# 16_BoardPowerSupply.net
KiCad netlist of a schematic drawn in Altium Designer
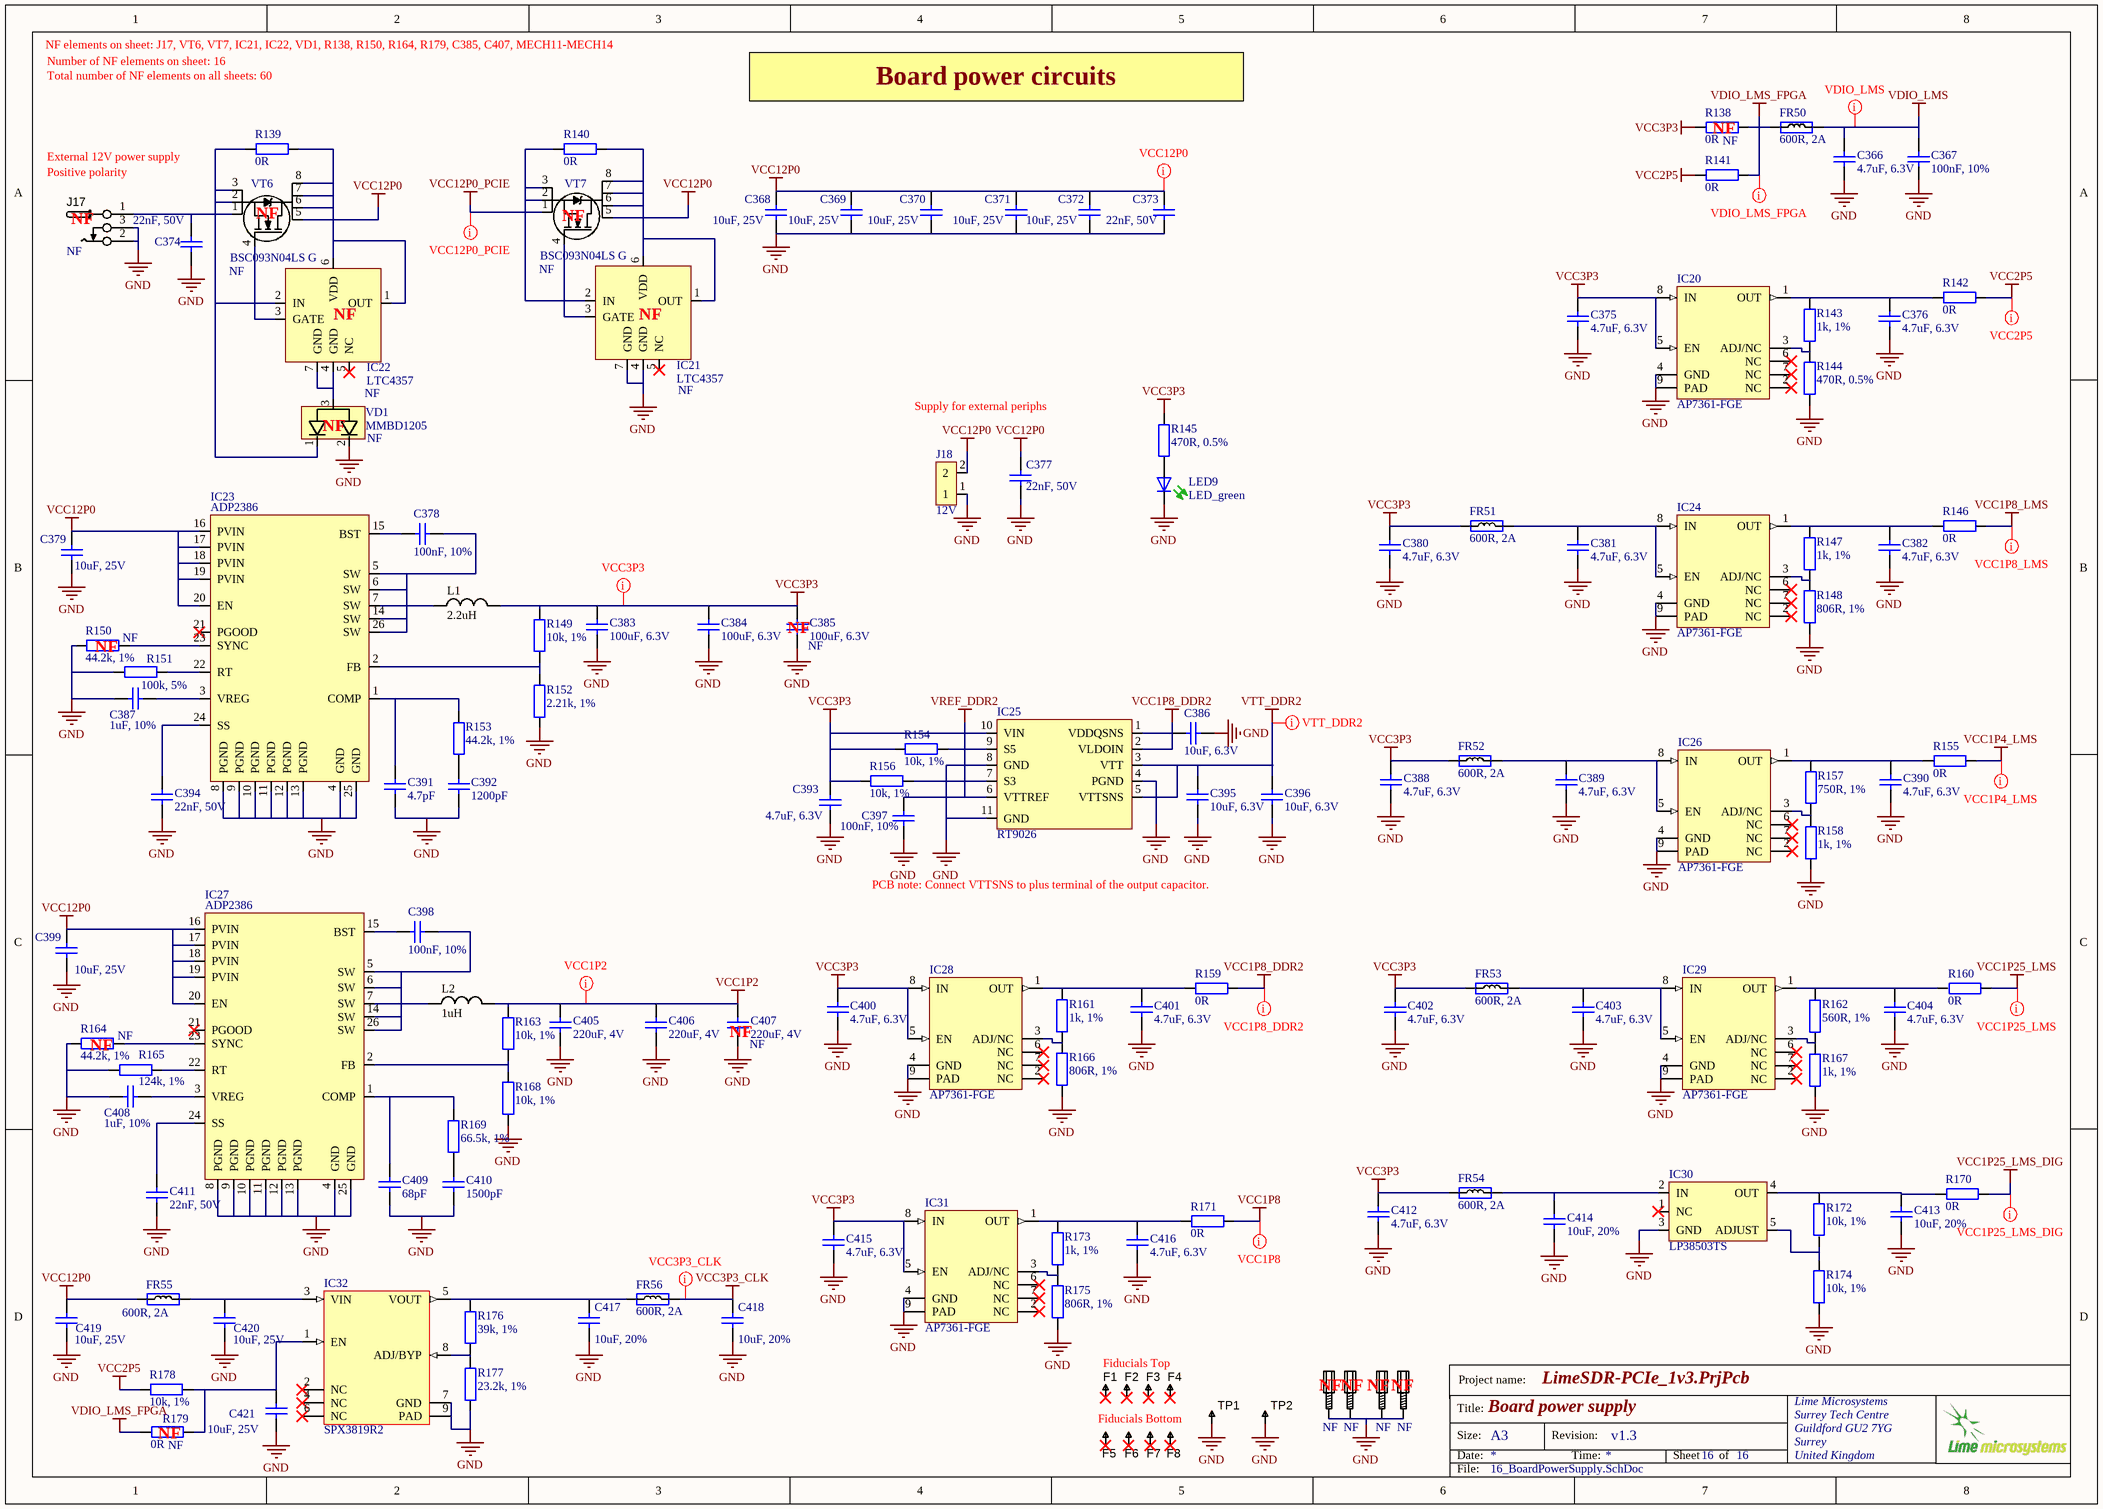
[diagram p0: 16_BoardPowerSupply.SchDoc]

(export (version "E")
  (design (tool "Eeschema 10.0.6"))
  (components
    (comp (ref "C366")
      (value "4.7uF, 6.3V")
      (footprint "CAP0402")
      (fields
        (field (name "MANUFACTURER") "Murata Electronics North America")
        (field (name "TOLERANCE") "±20%")
      )
      (libsource (lib "LimeMicroAltiumLib_schLib") (part "Cap_0402"))
    )
    (comp (ref "C367")
      (value "100nF, 10%")
      (footprint "CAP0402")
      (fields
        (field (name "MANUFACTURER") "Murata Electronics")
        (field (name "TOLERANCE") "10 %")
        (field (name "MANUFACTURER PART NUMBER") "GRM155R71C104KA88D")
      )
      (libsource (lib "LimeMicroAltiumLib_schLib") (part "Cap_0402"))
    )
    (comp (ref "C368")
      (value "10uF, 25V")
      (footprint "CAP0603")
      (fields
        (field (name "MANUFACTURER") "Murata Electronics North America")
        (field (name "MANUFACTURER PART NUMBER") "GRM188R61E106MA73D")
        (field (name "TOLERANCE") "±20%")
      )
      (libsource (lib "LimeMicroAltiumLib_schLib") (part "Cap_0603"))
    )
    (comp (ref "C369")
      (value "10uF, 25V")
      (footprint "CAP0603")
      (fields
        (field (name "MANUFACTURER") "Murata Electronics North America")
        (field (name "MANUFACTURER PART NUMBER") "GRM188R61E106MA73D")
        (field (name "TOLERANCE") "±20%")
      )
      (libsource (lib "LimeMicroAltiumLib_schLib") (part "Cap_0603"))
    )
    (comp (ref "C370")
      (value "10uF, 25V")
      (footprint "CAP0603")
      (fields
        (field (name "MANUFACTURER") "Murata Electronics North America")
        (field (name "MANUFACTURER PART NUMBER") "GRM188R61E106MA73D")
        (field (name "TOLERANCE") "±20%")
      )
      (libsource (lib "LimeMicroAltiumLib_schLib") (part "Cap_0603"))
    )
    (comp (ref "C371")
      (value "10uF, 25V")
      (footprint "CAP0603")
      (fields
        (field (name "MANUFACTURER") "Murata Electronics North America")
        (field (name "MANUFACTURER PART NUMBER") "GRM188R61E106MA73D")
        (field (name "TOLERANCE") "±20%")
      )
      (libsource (lib "LimeMicroAltiumLib_schLib") (part "Cap_0603"))
    )
    (comp (ref "C372")
      (value "10uF, 25V")
      (footprint "CAP0603")
      (fields
        (field (name "MANUFACTURER") "Murata Electronics North America")
        (field (name "MANUFACTURER PART NUMBER") "GRM188R61E106MA73D")
        (field (name "TOLERANCE") "±20%")
      )
      (libsource (lib "LimeMicroAltiumLib_schLib") (part "Cap_0603"))
    )
    (comp (ref "C373")
      (value "22nF, 50V")
      (footprint "CAP0402")
      (fields (field (name "TOLERANCE") "±10%") (field (name "MANUFACTURER") "Kemet"))
      (libsource (lib "LimeMicroAltiumLib_schLib") (part "Cap_0402"))
    )
    (comp (ref "C374")
      (value "22nF, 50V")
      (footprint "CAP0402")
      (fields (field (name "TOLERANCE") "±10%") (field (name "MANUFACTURER") "Kemet"))
      (libsource (lib "LimeMicroAltiumLib_schLib") (part "Cap_0402"))
    )
    (comp (ref "C375")
      (value "4.7uF, 6.3V")
      (footprint "CAP0402")
      (fields
        (field (name "MANUFACTURER") "Murata Electronics North America")
        (field (name "TOLERANCE") "±20%")
      )
      (libsource (lib "LimeMicroAltiumLib_schLib") (part "Cap_0402"))
    )
    (comp (ref "C376")
      (value "4.7uF, 6.3V")
      (footprint "CAP0402")
      (fields
        (field (name "MANUFACTURER") "Murata Electronics North America")
        (field (name "TOLERANCE") "±20%")
      )
      (libsource (lib "LimeMicroAltiumLib_schLib") (part "Cap_0402"))
    )
    (comp (ref "C377")
      (value "22nF, 50V")
      (footprint "CAP0402")
      (fields (field (name "TOLERANCE") "±10%") (field (name "MANUFACTURER") "Kemet"))
      (libsource (lib "LimeMicroAltiumLib_schLib") (part "Cap_0402"))
    )
    (comp (ref "C378")
      (value "100nF, 10%")
      (footprint "CAP0402")
      (fields
        (field (name "MANUFACTURER") "Murata Electronics")
        (field (name "TOLERANCE") "10 %")
        (field (name "MANUFACTURER PART NUMBER") "GRM155R71C104KA88D")
      )
      (libsource (lib "LimeMicroAltiumLib_schLib") (part "Cap_0402"))
    )
    (comp (ref "C379")
      (value "10uF, 25V")
      (footprint "CAP0603")
      (fields
        (field (name "MANUFACTURER") "Murata Electronics North America")
        (field (name "MANUFACTURER PART NUMBER") "GRM188R61E106MA73D")
        (field (name "TOLERANCE") "±20%")
      )
      (libsource (lib "LimeMicroAltiumLib_schLib") (part "Cap_0603"))
    )
    (comp (ref "C380")
      (value "4.7uF, 6.3V")
      (footprint "CAP0402")
      (fields
        (field (name "MANUFACTURER") "Murata Electronics North America")
        (field (name "TOLERANCE") "±20%")
      )
      (libsource (lib "LimeMicroAltiumLib_schLib") (part "Cap_0402"))
    )
    (comp (ref "C381")
      (value "4.7uF, 6.3V")
      (footprint "CAP0402")
      (fields
        (field (name "MANUFACTURER") "Murata Electronics North America")
        (field (name "TOLERANCE") "±20%")
      )
      (libsource (lib "LimeMicroAltiumLib_schLib") (part "Cap_0402"))
    )
    (comp (ref "C382")
      (value "4.7uF, 6.3V")
      (footprint "CAP0402")
      (fields
        (field (name "MANUFACTURER") "Murata Electronics North America")
        (field (name "TOLERANCE") "±20%")
      )
      (libsource (lib "LimeMicroAltiumLib_schLib") (part "Cap_0402"))
    )
    (comp (ref "C383")
      (value "100uF, 6.3V")
      (footprint "CAP1206")
      (fields (field (name "MANUFACTURER") "MURATA"))
      (libsource (lib "LimeFPGAboard_schLib") (part "Cap_1206"))
    )
    (comp (ref "C384")
      (value "100uF, 6.3V")
      (footprint "CAP1206")
      (fields (field (name "MANUFACTURER") "MURATA"))
      (libsource (lib "LimeFPGAboard_schLib") (part "Cap_1206"))
    )
    (comp (ref "C385")
      (value "100uF, 6.3V")
      (footprint "CAP1206")
      (fields (field (name "MANUFACTURER") "MURATA") (field (name "ASSEMBLY INFO") "NF"))
      (libsource (lib "LimeFPGAboard_schLib") (part "Cap_1206"))
    )
    (comp (ref "C386")
      (value "10uF, 6.3V")
      (footprint "CAP0603")
      (fields (field (name "TOLERANCE") "±20%") (field (name "MANUFACTURER") "Yageo"))
      (libsource (lib "LimeFPGAboard_schLib") (part "Cap_0603"))
    )
    (comp (ref "C387")
      (value "1uF, 10%")
      (footprint "CAP0402")
      (fields (field (name "MANUFACTURER") "TDK"))
      (libsource (lib "LimeMicroAltiumLib_schLib") (part "Cap_0402"))
    )
    (comp (ref "C388")
      (value "4.7uF, 6.3V")
      (footprint "CAP0402")
      (fields
        (field (name "MANUFACTURER") "Murata Electronics North America")
        (field (name "TOLERANCE") "±20%")
      )
      (libsource (lib "LimeMicroAltiumLib_schLib") (part "Cap_0402"))
    )
    (comp (ref "C389")
      (value "4.7uF, 6.3V")
      (footprint "CAP0402")
      (fields
        (field (name "MANUFACTURER") "Murata Electronics North America")
        (field (name "TOLERANCE") "±20%")
      )
      (libsource (lib "LimeMicroAltiumLib_schLib") (part "Cap_0402"))
    )
    (comp (ref "C390")
      (value "4.7uF, 6.3V")
      (footprint "CAP0402")
      (fields
        (field (name "MANUFACTURER") "Murata Electronics North America")
        (field (name "TOLERANCE") "±20%")
      )
      (libsource (lib "LimeMicroAltiumLib_schLib") (part "Cap_0402"))
    )
    (comp (ref "C391")
      (value "4.7pF")
      (footprint "CAP0402")
      (fields (field (name "MANUFACTURER") "MURATA"))
      (libsource (lib "LimeMicroAltiumLib_schLib") (part "Cap_0402"))
    )
    (comp (ref "C392")
      (value "1200pF")
      (footprint "CAP0402")
      (fields (field (name "MANUFACTURER") "Kemet") (field (name "TOLERANCE") "±5%"))
      (libsource (lib "LimeMicroAltiumLib_schLib") (part "Cap_0402"))
    )
    (comp (ref "C393")
      (value "4.7uF, 6.3V")
      (footprint "CAP0402")
      (fields
        (field (name "MANUFACTURER") "Murata Electronics North America")
        (field (name "TOLERANCE") "±20%")
      )
      (libsource (lib "LimeMicroAltiumLib_schLib") (part "Cap_0402"))
    )
    (comp (ref "C394")
      (value "22nF, 50V")
      (footprint "CAP0402")
      (fields (field (name "TOLERANCE") "±10%") (field (name "MANUFACTURER") "Kemet"))
      (libsource (lib "LimeMicroAltiumLib_schLib") (part "Cap_0402"))
    )
    (comp (ref "C395")
      (value "10uF, 6.3V")
      (footprint "CAP0603")
      (fields (field (name "TOLERANCE") "±20%") (field (name "MANUFACTURER") "Yageo"))
      (libsource (lib "LimeFPGAboard_schLib") (part "Cap_0603"))
    )
    (comp (ref "C396")
      (value "10uF, 6.3V")
      (footprint "CAP0603")
      (fields (field (name "TOLERANCE") "±20%") (field (name "MANUFACTURER") "Yageo"))
      (libsource (lib "LimeFPGAboard_schLib") (part "Cap_0603"))
    )
    (comp (ref "C397")
      (value "100nF, 10%")
      (footprint "CAP0402")
      (fields
        (field (name "MANUFACTURER") "Murata Electronics")
        (field (name "TOLERANCE") "10 %")
        (field (name "MANUFACTURER PART NUMBER") "GRM155R71C104KA88D")
      )
      (libsource (lib "LimeMicroAltiumLib_schLib") (part "Cap_0402"))
    )
    (comp (ref "C398")
      (value "100nF, 10%")
      (footprint "CAP0402")
      (fields
        (field (name "MANUFACTURER") "Murata Electronics")
        (field (name "TOLERANCE") "10 %")
        (field (name "MANUFACTURER PART NUMBER") "GRM155R71C104KA88D")
      )
      (libsource (lib "LimeMicroAltiumLib_schLib") (part "Cap_0402"))
    )
    (comp (ref "C399")
      (value "10uF, 25V")
      (footprint "CAP0603")
      (fields
        (field (name "MANUFACTURER") "Murata Electronics North America")
        (field (name "MANUFACTURER PART NUMBER") "GRM188R61E106MA73D")
        (field (name "TOLERANCE") "±20%")
      )
      (libsource (lib "LimeMicroAltiumLib_schLib") (part "Cap_0603"))
    )
    (comp (ref "C400")
      (value "4.7uF, 6.3V")
      (footprint "CAP0402")
      (fields
        (field (name "MANUFACTURER") "Murata Electronics North America")
        (field (name "TOLERANCE") "±20%")
      )
      (libsource (lib "LimeMicroAltiumLib_schLib") (part "Cap_0402"))
    )
    (comp (ref "C401")
      (value "4.7uF, 6.3V")
      (footprint "CAP0402")
      (fields
        (field (name "MANUFACTURER") "Murata Electronics North America")
        (field (name "TOLERANCE") "±20%")
      )
      (libsource (lib "LimeMicroAltiumLib_schLib") (part "Cap_0402"))
    )
    (comp (ref "C402")
      (value "4.7uF, 6.3V")
      (footprint "CAP0402")
      (fields
        (field (name "MANUFACTURER") "Murata Electronics North America")
        (field (name "TOLERANCE") "±20%")
      )
      (libsource (lib "LimeMicroAltiumLib_schLib") (part "Cap_0402"))
    )
    (comp (ref "C403")
      (value "4.7uF, 6.3V")
      (footprint "CAP0402")
      (fields
        (field (name "MANUFACTURER") "Murata Electronics North America")
        (field (name "TOLERANCE") "±20%")
      )
      (libsource (lib "LimeMicroAltiumLib_schLib") (part "Cap_0402"))
    )
    (comp (ref "C404")
      (value "4.7uF, 6.3V")
      (footprint "CAP0402")
      (fields
        (field (name "MANUFACTURER") "Murata Electronics North America")
        (field (name "TOLERANCE") "±20%")
      )
      (libsource (lib "LimeMicroAltiumLib_schLib") (part "Cap_0402"))
    )
    (comp (ref "C405")
      (value "220uF, 4V")
      (footprint "CAP1206")
      (fields
        (field (name "MANUFACTURER PART NUMBER") "GRM31CR60G227ME11L")
        (field (name "MANUFACTURER") "Murata Electronics North America")
        (field (name "TOLERANCE") "±20%")
      )
      (libsource (lib "LimeFPGAboard_schLib") (part "Cap_1206"))
    )
    (comp (ref "C406")
      (value "220uF, 4V")
      (footprint "CAP1206")
      (fields
        (field (name "MANUFACTURER PART NUMBER") "GRM31CR60G227ME11L")
        (field (name "MANUFACTURER") "Murata Electronics North America")
        (field (name "TOLERANCE") "±20%")
      )
      (libsource (lib "LimeFPGAboard_schLib") (part "Cap_1206"))
    )
    (comp (ref "C407")
      (value "220uF, 4V")
      (footprint "CAP1206")
      (fields
        (field (name "MANUFACTURER PART NUMBER") "GRM31CR60G227ME11L")
        (field (name "MANUFACTURER") "Murata Electronics North America")
        (field (name "TOLERANCE") "±20%")
        (field (name "ASSEMBLY INFO") "NF")
      )
      (libsource (lib "LimeFPGAboard_schLib") (part "Cap_1206"))
    )
    (comp (ref "C408")
      (value "1uF, 10%")
      (footprint "CAP0402")
      (fields (field (name "MANUFACTURER") "TDK"))
      (libsource (lib "LimeMicroAltiumLib_schLib") (part "Cap_0402"))
    )
    (comp (ref "C409")
      (value "68pF")
      (footprint "CAP0402")
      (fields (field (name "TOLERANCE") "±1%") (field (name "MANUFACTURER") "Kemet"))
      (libsource (lib "LimeMicroAltiumLib_schLib") (part "Cap_0402"))
    )
    (comp (ref "C410")
      (value "1500pF")
      (footprint "CAP0402")
      (fields
        (field (name "MANUFACTURER") "Samsung Electro-Mechanics America, Inc.")
        (field (name "TOLERANCE") "±10%")
      )
      (libsource (lib "LimeMicroAltiumLib_schLib") (part "Cap_0402"))
    )
    (comp (ref "C411")
      (value "22nF, 50V")
      (footprint "CAP0402")
      (fields (field (name "TOLERANCE") "±10%") (field (name "MANUFACTURER") "Kemet"))
      (libsource (lib "LimeMicroAltiumLib_schLib") (part "Cap_0402"))
    )
    (comp (ref "C412")
      (value "4.7uF, 6.3V")
      (footprint "CAP0402")
      (fields
        (field (name "MANUFACTURER") "Murata Electronics North America")
        (field (name "TOLERANCE") "±20%")
      )
      (libsource (lib "LimeMicroAltiumLib_schLib") (part "Cap_0402"))
    )
    (comp (ref "C413")
      (value "10uF, 20%")
      (footprint "CAP0603")
      (fields (field (name "MANUFACTURER") "Yageo") (field (name "TOLERANCE") "±20%"))
      (libsource (lib "LimeMicroAltiumLib_schLib") (part "Cap_0603"))
    )
    (comp (ref "C414")
      (value "10uF, 20%")
      (footprint "CAP0603")
      (fields (field (name "MANUFACTURER") "Yageo") (field (name "TOLERANCE") "±20%"))
      (libsource (lib "LimeMicroAltiumLib_schLib") (part "Cap_0603"))
    )
    (comp (ref "C415")
      (value "4.7uF, 6.3V")
      (footprint "CAP0402")
      (fields
        (field (name "MANUFACTURER") "Murata Electronics North America")
        (field (name "TOLERANCE") "±20%")
      )
      (libsource (lib "LimeMicroAltiumLib_schLib") (part "Cap_0402"))
    )
    (comp (ref "C416")
      (value "4.7uF, 6.3V")
      (footprint "CAP0402")
      (fields
        (field (name "MANUFACTURER") "Murata Electronics North America")
        (field (name "TOLERANCE") "±20%")
      )
      (libsource (lib "LimeMicroAltiumLib_schLib") (part "Cap_0402"))
    )
    (comp (ref "C417")
      (value "10uF, 20%")
      (footprint "CAP0603")
      (fields (field (name "MANUFACTURER") "Yageo") (field (name "TOLERANCE") "±20%"))
      (libsource (lib "LimeMicroAltiumLib_schLib") (part "Cap_0603"))
    )
    (comp (ref "C418")
      (value "10uF, 20%")
      (footprint "CAP0603")
      (fields (field (name "MANUFACTURER") "Yageo") (field (name "TOLERANCE") "±20%"))
      (libsource (lib "LimeMicroAltiumLib_schLib") (part "Cap_0603"))
    )
    (comp (ref "C419")
      (value "10uF, 25V")
      (footprint "CAP0603")
      (fields
        (field (name "MANUFACTURER") "Murata Electronics North America")
        (field (name "MANUFACTURER PART NUMBER") "GRM188R61E106MA73D")
        (field (name "TOLERANCE") "±20%")
      )
      (libsource (lib "LimeMicroAltiumLib_schLib") (part "Cap_0603"))
    )
    (comp (ref "C420")
      (value "10uF, 25V")
      (footprint "CAP0603")
      (fields
        (field (name "MANUFACTURER") "Murata Electronics North America")
        (field (name "MANUFACTURER PART NUMBER") "GRM188R61E106MA73D")
        (field (name "TOLERANCE") "±20%")
      )
      (libsource (lib "LimeMicroAltiumLib_schLib") (part "Cap_0603"))
    )
    (comp (ref "C421")
      (value "10uF, 25V")
      (footprint "CAP0603")
      (fields
        (field (name "MANUFACTURER") "Murata Electronics North America")
        (field (name "MANUFACTURER PART NUMBER") "GRM188R61E106MA73D")
        (field (name "TOLERANCE") "±20%")
      )
      (libsource (lib "LimeMicroAltiumLib_schLib") (part "Cap_0603"))
    )
    (comp (ref "F1")
      (value "Fiducial")
      (footprint "Fiducial")
      (libsource (lib "LimeMicroAltiumLib_schLib") (part "Fiducial"))
    )
    (comp (ref "F2")
      (value "Fiducial")
      (footprint "Fiducial")
      (libsource (lib "LimeMicroAltiumLib_schLib") (part "Fiducial"))
    )
    (comp (ref "F3")
      (value "Fiducial")
      (footprint "Fiducial")
      (libsource (lib "LimeMicroAltiumLib_schLib") (part "Fiducial"))
    )
    (comp (ref "F4")
      (value "Fiducial")
      (footprint "Fiducial")
      (libsource (lib "LimeMicroAltiumLib_schLib") (part "Fiducial"))
    )
    (comp (ref "F5")
      (value "Fiducial")
      (footprint "Fiducial")
      (libsource (lib "VGTU_Altium_lib") (part "Fiducial"))
    )
    (comp (ref "F6")
      (value "Fiducial")
      (footprint "Fiducial")
      (libsource (lib "VGTU_Altium_lib") (part "Fiducial"))
    )
    (comp (ref "F7")
      (value "Fiducial")
      (footprint "Fiducial")
      (libsource (lib "VGTU_Altium_lib") (part "Fiducial"))
    )
    (comp (ref "F8")
      (value "Fiducial")
      (footprint "Fiducial")
      (libsource (lib "VGTU_Altium_lib") (part "Fiducial"))
    )
    (comp (ref "FR50")
      (value "600R, 2A")
      (footprint "RES0805")
      (fields (field (name "MANUFACTURER") "TDK Corporation"))
      (libsource (lib "LimeMicroAltiumLib_schLib") (part "Ferrite"))
    )
    (comp (ref "FR51")
      (value "600R, 2A")
      (footprint "RES0805")
      (fields (field (name "MANUFACTURER") "TDK Corporation"))
      (libsource (lib "LimeMicroAltiumLib_schLib") (part "Ferrite"))
    )
    (comp (ref "FR52")
      (value "600R, 2A")
      (footprint "RES0805")
      (fields (field (name "MANUFACTURER") "TDK Corporation"))
      (libsource (lib "LimeMicroAltiumLib_schLib") (part "Ferrite"))
    )
    (comp (ref "FR53")
      (value "600R, 2A")
      (footprint "RES0805")
      (fields (field (name "MANUFACTURER") "TDK Corporation"))
      (libsource (lib "LimeMicroAltiumLib_schLib") (part "Ferrite"))
    )
    (comp (ref "FR54")
      (value "600R, 2A")
      (footprint "RES0805")
      (fields (field (name "MANUFACTURER") "TDK Corporation"))
      (libsource (lib "LimeMicroAltiumLib_schLib") (part "Ferrite"))
    )
    (comp (ref "FR55")
      (value "600R, 2A")
      (footprint "RES0805")
      (fields (field (name "MANUFACTURER") "TDK Corporation"))
      (libsource (lib "LimeMicroAltiumLib_schLib") (part "Ferrite"))
    )
    (comp (ref "FR56")
      (value "600R, 2A")
      (footprint "RES0805")
      (fields (field (name "MANUFACTURER") "TDK Corporation"))
      (libsource (lib "LimeMicroAltiumLib_schLib") (part "Ferrite"))
    )
    (comp (ref "IC20")
      (value "AP7361-FGE")
      (footprint "AP7361")
      (fields
        (field (name "MANUFACTURER PART NUMBER") "AP7361-FGE-7")
        (field (name "MANUFACTURER") "Diodes Incorporated")
      )
      (libsource (lib "LimeMicroAltiumLib_schLib") (part "AP7361"))
    )
    (comp (ref "IC21")
      (value "LTC4357")
      (footprint "LTC4357")
      (fields
        (field (name "MANUFACTURER PART NUMBER") "LTC4357IDCB#TRMPBF")
        (field (name "MANUFACTURER") "Linear Technology")
        (field (name "ASSEMBLY INFO") "NF")
      )
      (libsource (lib "LimeFPGAboard_schLib") (part "LTC4357"))
    )
    (comp (ref "IC22")
      (value "LTC4357")
      (footprint "LTC4357")
      (fields
        (field (name "MANUFACTURER PART NUMBER") "LTC4357IDCB#TRMPBF")
        (field (name "MANUFACTURER") "Linear Technology")
        (field (name "ASSEMBLY INFO") "NF")
      )
      (libsource (lib "LimeFPGAboard_schLib") (part "LTC4357"))
    )
    (comp (ref "IC23")
      (value "ADP2386")
      (footprint "ADP2386")
      (fields
        (field (name "MANUFACTURER PART NUMBER") "ADP2386ACPZN-R7")
        (field (name "MANUFACTURER") "Analog Devices Inc.")
      )
      (libsource (lib "LimeMicroAltiumLib_schLib") (part "ADP2386"))
    )
    (comp (ref "IC24")
      (value "AP7361-FGE")
      (footprint "AP7361")
      (fields
        (field (name "MANUFACTURER PART NUMBER") "AP7361-FGE-7")
        (field (name "MANUFACTURER") "Diodes Incorporated")
      )
      (libsource (lib "LimeMicroAltiumLib_schLib") (part "AP7361"))
    )
    (comp (ref "IC25")
      (value "RT9026")
      (footprint "MSOP10")
      (fields (field (name "MANUFACTURER") "Richtek USA Inc."))
      (libsource (lib "LimeMicroAltiumLib_schLib") (part "RT9026"))
    )
    (comp (ref "IC26")
      (value "AP7361-FGE")
      (footprint "AP7361")
      (fields
        (field (name "MANUFACTURER PART NUMBER") "AP7361-FGE-7")
        (field (name "MANUFACTURER") "Diodes Incorporated")
      )
      (libsource (lib "LimeMicroAltiumLib_schLib") (part "AP7361"))
    )
    (comp (ref "IC27")
      (value "ADP2386")
      (footprint "ADP2386")
      (fields (field (name "MANUFACTURER") "Analog Devices Inc."))
      (libsource (lib "LimeMicroAltiumLib_schLib") (part "ADP2386"))
    )
    (comp (ref "IC28")
      (value "AP7361-FGE")
      (footprint "AP7361")
      (fields
        (field (name "MANUFACTURER PART NUMBER") "AP7361-FGE-7")
        (field (name "MANUFACTURER") "Diodes Incorporated")
      )
      (libsource (lib "LimeMicroAltiumLib_schLib") (part "AP7361"))
    )
    (comp (ref "IC29")
      (value "AP7361-FGE")
      (footprint "AP7361")
      (fields
        (field (name "MANUFACTURER PART NUMBER") "AP7361-FGE-7")
        (field (name "MANUFACTURER") "Diodes Incorporated")
      )
      (libsource (lib "LimeMicroAltiumLib_schLib") (part "AP7361"))
    )
    (comp (ref "IC30")
      (value "LP38503TS")
      (footprint "TO-263-5_v2")
      (fields
        (field (name "MANUFACTURER PART NUMBER") "LP38503TS-ADJ/NOPB")
        (field (name "MANUFACTURER") "Texas Instruments")
      )
      (libsource (lib "LimeMicroAltiumLib_schLib") (part "LP38503TS"))
    )
    (comp (ref "IC31")
      (value "AP7361-FGE")
      (footprint "AP7361")
      (fields
        (field (name "MANUFACTURER PART NUMBER") "AP7361-FGE-7")
        (field (name "MANUFACTURER") "Diodes Incorporated")
      )
      (libsource (lib "LimeMicroAltiumLib_schLib") (part "AP7361"))
    )
    (comp (ref "IC32")
      (value "SPX3819R2")
      (footprint "SPX3819R2-L/TR")
      (fields (field (name "MANUFACTURER") "Exar Corporation"))
      (libsource (lib "LimeMicroAltiumLib_schLib") (part "SPX3819R2-L/TR"))
    )
    (comp (ref "J17")
      (value "CONN_PWR_JACK_2.1x5.5mm")
      (footprint "CONN_PWR_JACK_v2")
      (description "Power Connector, THT, 2.1mm ID, 5.5mm OD")
      (fields (field (name "MANUFACTURER") "SWITCHCRAFT") (field (name "ASSEMBLY INFO") "NF"))
      (libsource (lib "LimeFPGAboard_schLib") (part "CONN_PWR_JACK_2.1x5.5mm"))
    )
    (comp (ref "J18")
      (value "12V")
      (footprint "HDR_1x2")
      (fields (field (name "MANUFACTURER") "3M"))
      (libsource (lib "LimeFPGAboard_schLib") (part "Jumper"))
    )
    (comp (ref "L1")
      (value "2.2uH")
      (footprint "FDVE1040_TOKO_INDUCTOR")
      (fields (field (name "TOLERANCE") "±20%") (field (name "MANUFACTURER") "Vishay Dale"))
      (libsource (lib "LimeMicroAltiumLib_schLib") (part "Inductor_0603"))
    )
    (comp (ref "L2")
      (value "1uH")
      (footprint "FDVE1040_TOKO_INDUCTOR")
      (fields (field (name "TOLERANCE") "±20%") (field (name "MANUFACTURER") "Vishay Dale"))
      (libsource (lib "LimeMicroAltiumLib_schLib") (part "Inductor_0603"))
    )
    (comp (ref "LED9")
      (value "LED_green")
      (footprint "LED-0603-GREEN")
      (fields (field (name "MANUFACTURER") "Broadcom Limited"))
      (libsource (lib "LimeFPGAboard_schLib") (part "LED_green"))
    )
    (comp (ref "MECH11")
      (value "# pcs.")
      (footprint "PCB_standoff")
      (description "STANDOFF M/F MET 5MM HEX 10MM L")
      (fields (field (name "MANUFACTURER") "Keystone Electronics") (field (name "ASSEMBLY INFO") "NF"))
      (libsource (lib "LimeMicroAltiumLib_schLib") (part "STANDOFF_M-F_THREADED_M3x8x10mm_HEX_5mm dia"))
    )
    (comp (ref "MECH12")
      (value "# pcs.")
      (footprint "PCB_standoff")
      (description "STANDOFF M/F MET 5MM HEX 10MM L")
      (fields (field (name "MANUFACTURER") "Keystone Electronics") (field (name "ASSEMBLY INFO") "NF"))
      (libsource (lib "LimeMicroAltiumLib_schLib") (part "STANDOFF_M-F_THREADED_M3x8x10mm_HEX_5mm dia"))
    )
    (comp (ref "MECH13")
      (value "# pcs.")
      (footprint "PCB_standoff")
      (description "STANDOFF M/F MET 5MM HEX 10MM L")
      (fields (field (name "MANUFACTURER") "Keystone Electronics") (field (name "ASSEMBLY INFO") "NF"))
      (libsource (lib "LimeMicroAltiumLib_schLib") (part "STANDOFF_M-F_THREADED_M3x8x10mm_HEX_5mm dia"))
    )
    (comp (ref "MECH14")
      (value "# pcs.")
      (footprint "PCB_standoff")
      (description "STANDOFF M/F MET 5MM HEX 10MM L")
      (fields (field (name "MANUFACTURER") "Keystone Electronics") (field (name "ASSEMBLY INFO") "NF"))
      (libsource (lib "LimeMicroAltiumLib_schLib") (part "STANDOFF_M-F_THREADED_M3x8x10mm_HEX_5mm dia"))
    )
    (comp (ref "R138")
      (value "0R")
      (footprint "RES0402")
      (fields
        (field (name "ASSEMBLY INFO") "NF")
        (field (name "MANUFACTURER") "Yageo")
        (field (name "TOLERANCE") "Jumper")
      )
      (libsource (lib "LimeMicroAltiumLib_schLib") (part "Res_0402"))
    )
    (comp (ref "R139")
      (value "0R")
      (footprint "RES0805")
      (fields (field (name "MANUFACTURER") "Vishay Dale") (field (name "TOLERANCE") "Jumper"))
      (libsource (lib "LimeMicroAltiumLib_schLib") (part "Res_0402"))
    )
    (comp (ref "R140")
      (value "0R")
      (footprint "RES0805")
      (fields (field (name "MANUFACTURER") "Vishay Dale") (field (name "TOLERANCE") "Jumper"))
      (libsource (lib "LimeMicroAltiumLib_schLib") (part "Res_0402"))
    )
    (comp (ref "R141")
      (value "0R")
      (footprint "RES0402")
      (fields (field (name "MANUFACTURER") "Yageo") (field (name "TOLERANCE") "Jumper"))
      (libsource (lib "LimeMicroAltiumLib_schLib") (part "Res_0402"))
    )
    (comp (ref "R142")
      (value "0R")
      (footprint "RES0402")
      (fields (field (name "MANUFACTURER") "Yageo") (field (name "TOLERANCE") "Jumper"))
      (libsource (lib "LimeMicroAltiumLib_schLib") (part "Res_0402"))
    )
    (comp (ref "R143")
      (value "1k, 1%")
      (footprint "RES0402")
      (fields (field (name "MANUFACTURER") "Stackpole Electronics Inc") (field (name "TOLERANCE") "±1%"))
      (libsource (lib "LimeMicroAltiumLib_schLib") (part "Res_0402"))
    )
    (comp (ref "R144")
      (value "470R, 0.5%")
      (footprint "RES0402")
      (fields
        (field (name "TOLERANCE") "±0.5%")
        (field (name "MANUFACTURER") "Panasonic Electronic Components")
      )
      (libsource (lib "LimeMicroAltiumLib_schLib") (part "Res_0402"))
    )
    (comp (ref "R145")
      (value "470R, 0.5%")
      (footprint "RES0402")
      (fields (field (name "TOLERANCE") "±0.5%"))
      (libsource (lib "LimeFPGAboard_schLib") (part "Res_0402"))
    )
    (comp (ref "R146")
      (value "0R")
      (footprint "RES0402")
      (fields (field (name "MANUFACTURER") "Yageo") (field (name "TOLERANCE") "Jumper"))
      (libsource (lib "LimeMicroAltiumLib_schLib") (part "Res_0402"))
    )
    (comp (ref "R147")
      (value "1k, 1%")
      (footprint "RES0402")
      (fields (field (name "MANUFACTURER") "Stackpole Electronics Inc") (field (name "TOLERANCE") "±1%"))
      (libsource (lib "LimeMicroAltiumLib_schLib") (part "Res_0402"))
    )
    (comp (ref "R148")
      (value "806R, 1%")
      (footprint "RES0402")
      (fields (field (name "TOLERANCE") "±1%") (field (name "MANUFACTURER") "Stackpole Electronics Inc"))
      (libsource (lib "LimeMicroAltiumLib_schLib") (part "Res_0402"))
    )
    (comp (ref "R149")
      (value "10k, 1%")
      (footprint "RES0402")
      (fields (field (name "MANUFACTURER") "Yageo") (field (name "TOLERANCE") "±1%"))
      (libsource (lib "LimeMicroAltiumLib_schLib") (part "Res_0402"))
    )
    (comp (ref "R150")
      (value "44.2k, 1%")
      (footprint "RES0402")
      (fields
        (field (name "ASSEMBLY INFO") "NF")
        (field (name "TOLERANCE") "±1%")
        (field (name "MANUFACTURER") "Panasonic Electronic Components")
      )
      (libsource (lib "LimeMicroAltiumLib_schLib") (part "Res_0402"))
    )
    (comp (ref "R151")
      (value "100k, 5%")
      (footprint "RES0402")
      (fields
        (field (name "MANUFACTURER") "Panasonic Electronic Components")
        (field (name "MANUFACTURER PART NUMBER") "ERJ-2GEJ104X")
        (field (name "TOLERANCE") "±5%")
      )
      (libsource (lib "LimeMicroAltiumLib_schLib") (part "Res_0402"))
    )
    (comp (ref "R152")
      (value "2.21k, 1%")
      (footprint "RES0402")
      (fields (field (name "MANUFACTURER") "Stackpole Electronics Inc.") (field (name "TOLERANCE") "±1%"))
      (libsource (lib "LimeMicroAltiumLib_schLib") (part "Res_0402"))
    )
    (comp (ref "R153")
      (value "44.2k, 1%")
      (footprint "RES0402")
      (fields
        (field (name "TOLERANCE") "±1%")
        (field (name "MANUFACTURER") "Panasonic Electronic Components")
      )
      (libsource (lib "LimeMicroAltiumLib_schLib") (part "Res_0402"))
    )
    (comp (ref "R154")
      (value "10k, 1%")
      (footprint "RES0402")
      (fields (field (name "MANUFACTURER") "Yageo") (field (name "TOLERANCE") "±1%"))
      (libsource (lib "LimeMicroAltiumLib_schLib") (part "Res_0402"))
    )
    (comp (ref "R155")
      (value "0R")
      (footprint "RES0402")
      (fields (field (name "MANUFACTURER") "Yageo") (field (name "TOLERANCE") "Jumper"))
      (libsource (lib "LimeMicroAltiumLib_schLib") (part "Res_0402"))
    )
    (comp (ref "R156")
      (value "10k, 1%")
      (footprint "RES0402")
      (fields (field (name "MANUFACTURER") "Yageo") (field (name "TOLERANCE") "±1%"))
      (libsource (lib "LimeMicroAltiumLib_schLib") (part "Res_0402"))
    )
    (comp (ref "R157")
      (value "750R, 1%")
      (footprint "RES0402")
      (fields
        (field (name "TOLERANCE") "±1%")
        (field (name "MANUFACTURER PART NUMBER") "RC0402FR-07750RL")
        (field (name "MANUFACTURER") "Yageo")
      )
      (libsource (lib "LimeMicroAltiumLib_schLib") (part "Res_0402"))
    )
    (comp (ref "R158")
      (value "1k, 1%")
      (footprint "RES0402")
      (fields (field (name "MANUFACTURER") "Stackpole Electronics Inc") (field (name "TOLERANCE") "±1%"))
      (libsource (lib "LimeMicroAltiumLib_schLib") (part "Res_0402"))
    )
    (comp (ref "R159")
      (value "0R")
      (footprint "RES0402")
      (fields (field (name "MANUFACTURER") "Yageo") (field (name "TOLERANCE") "Jumper"))
      (libsource (lib "LimeMicroAltiumLib_schLib") (part "Res_0402"))
    )
    (comp (ref "R160")
      (value "0R")
      (footprint "RES0402")
      (fields (field (name "MANUFACTURER") "Yageo") (field (name "TOLERANCE") "Jumper"))
      (libsource (lib "LimeMicroAltiumLib_schLib") (part "Res_0402"))
    )
    (comp (ref "R161")
      (value "1k, 1%")
      (footprint "RES0402")
      (fields (field (name "MANUFACTURER") "Stackpole Electronics Inc") (field (name "TOLERANCE") "±1%"))
      (libsource (lib "LimeMicroAltiumLib_schLib") (part "Res_0402"))
    )
    (comp (ref "R162")
      (value "560R, 1%")
      (footprint "RES0402")
      (fields
        (field (name "MANUFACTURER PART NUMBER") "CRCW0402560RFKED")
        (field (name "TOLERANCE") "±1%")
        (field (name "MANUFACTURER") "Vishay Dale")
      )
      (libsource (lib "LimeMicroAltiumLib_schLib") (part "Res_0402"))
    )
    (comp (ref "R163")
      (value "10k, 1%")
      (footprint "RES0402")
      (fields (field (name "MANUFACTURER") "Yageo") (field (name "TOLERANCE") "±1%"))
      (libsource (lib "LimeMicroAltiumLib_schLib") (part "Res_0402"))
    )
    (comp (ref "R164")
      (value "44.2k, 1%")
      (footprint "RES0402")
      (fields
        (field (name "ASSEMBLY INFO") "NF")
        (field (name "TOLERANCE") "±1%")
        (field (name "MANUFACTURER") "Panasonic Electronic Components")
      )
      (libsource (lib "LimeMicroAltiumLib_schLib") (part "Res_0402"))
    )
    (comp (ref "R165")
      (value "124k, 1%")
      (footprint "RES0402")
      (fields
        (field (name "MANUFACTURER") "Panasonic Electronic Components")
        (field (name "TOLERANCE") "±1%")
      )
      (libsource (lib "LimeMicroAltiumLib_schLib") (part "Res_0402"))
    )
    (comp (ref "R166")
      (value "806R, 1%")
      (footprint "RES0402")
      (fields (field (name "TOLERANCE") "±1%") (field (name "MANUFACTURER") "Stackpole Electronics Inc"))
      (libsource (lib "LimeMicroAltiumLib_schLib") (part "Res_0402"))
    )
    (comp (ref "R167")
      (value "1k, 1%")
      (footprint "RES0402")
      (fields (field (name "MANUFACTURER") "Stackpole Electronics Inc") (field (name "TOLERANCE") "±1%"))
      (libsource (lib "LimeMicroAltiumLib_schLib") (part "Res_0402"))
    )
    (comp (ref "R168")
      (value "10k, 1%")
      (footprint "RES0402")
      (fields (field (name "MANUFACTURER") "Yageo") (field (name "TOLERANCE") "±1%"))
      (libsource (lib "LimeMicroAltiumLib_schLib") (part "Res_0402"))
    )
    (comp (ref "R169")
      (value "66.5k, 1%")
      (footprint "RES0402")
      (fields
        (field (name "MANUFACTURER") "Panasonic Electronic Components")
        (field (name "TOLERANCE") "±1%")
      )
      (libsource (lib "LimeMicroAltiumLib_schLib") (part "Res_0402"))
    )
    (comp (ref "R170")
      (value "0R")
      (footprint "RES0402")
      (fields (field (name "MANUFACTURER") "Yageo") (field (name "TOLERANCE") "Jumper"))
      (libsource (lib "LimeMicroAltiumLib_schLib") (part "Res_0402"))
    )
    (comp (ref "R171")
      (value "0R")
      (footprint "RES0402")
      (fields (field (name "MANUFACTURER") "Yageo") (field (name "TOLERANCE") "Jumper"))
      (libsource (lib "LimeMicroAltiumLib_schLib") (part "Res_0402"))
    )
    (comp (ref "R172")
      (value "10k, 1%")
      (footprint "RES0402")
      (fields (field (name "MANUFACTURER") "Yageo") (field (name "TOLERANCE") "±1%"))
      (libsource (lib "LimeMicroAltiumLib_schLib") (part "Res_0402"))
    )
    (comp (ref "R173")
      (value "1k, 1%")
      (footprint "RES0402")
      (fields (field (name "MANUFACTURER") "Stackpole Electronics Inc") (field (name "TOLERANCE") "±1%"))
      (libsource (lib "LimeMicroAltiumLib_schLib") (part "Res_0402"))
    )
    (comp (ref "R174")
      (value "10k, 1%")
      (footprint "RES0402")
      (fields (field (name "MANUFACTURER") "Yageo") (field (name "TOLERANCE") "±1%"))
      (libsource (lib "LimeMicroAltiumLib_schLib") (part "Res_0402"))
    )
    (comp (ref "R175")
      (value "806R, 1%")
      (footprint "RES0402")
      (fields (field (name "TOLERANCE") "±1%") (field (name "MANUFACTURER") "Stackpole Electronics Inc"))
      (libsource (lib "LimeMicroAltiumLib_schLib") (part "Res_0402"))
    )
    (comp (ref "R176")
      (value "39k, 1%")
      (footprint "RES0402")
      (fields (field (name "MANUFACTURER") "Yageo") (field (name "TOLERANCE") "±1%"))
      (libsource (lib "LimeMicroAltiumLib_schLib") (part "Res_0402"))
    )
    (comp (ref "R177")
      (value "23.2k, 1%")
      (footprint "RES0402")
      (fields (field (name "TOLERANCE") "±1%") (field (name "MANUFACTURER") "Yageo"))
      (libsource (lib "LimeMicroAltiumLib_schLib") (part "Res_0402"))
    )
    (comp (ref "R178")
      (value "10k, 1%")
      (footprint "RES0402")
      (fields (field (name "MANUFACTURER") "Yageo") (field (name "TOLERANCE") "±1%"))
      (libsource (lib "LimeMicroAltiumLib_schLib") (part "Res_0402"))
    )
    (comp (ref "R179")
      (value "0R")
      (footprint "RES0402")
      (fields
        (field (name "ASSEMBLY INFO") "NF")
        (field (name "MANUFACTURER") "Yageo")
        (field (name "TOLERANCE") "Jumper")
      )
      (libsource (lib "LimeMicroAltiumLib_schLib") (part "Res_0402"))
    )
    (comp (ref "TP1")
      (value "TESTPOINT_THT_MINI")
      (footprint "TP-THT-MIDI")
      (description "Test Point PCB mount Miniature White")
      (fields (field (name "MANUFACTURER") "Keystone Electronics"))
      (libsource (lib "LimeMicroAltiumLib_schLib") (part "TESTPOINT_THT_MINI"))
    )
    (comp (ref "TP2")
      (value "TESTPOINT_THT_MINI")
      (footprint "TP-THT-MIDI")
      (description "Test Point PCB mount Miniature White")
      (fields (field (name "MANUFACTURER") "Keystone Electronics"))
      (libsource (lib "LimeMicroAltiumLib_schLib") (part "TESTPOINT_THT_MINI"))
    )
    (comp (ref "VD1")
      (value "MMBD1205")
      (footprint "SOT23-3_v2")
      (fields (field (name "MANUFACTURER") "FAIRCHILD SEMICONDUCTOR") (field (name "ASSEMBLY INFO") "NF"))
      (libsource (lib "LimeFPGAboard_schLib") (part "MMBD1205"))
    )
    (comp (ref "VT6")
      (value "BSC093N04LS G")
      (footprint "BSC093N04LS_G")
      (fields (field (name "MANUFACTURER") "Infineon Technologies") (field (name "ASSEMBLY INFO") "NF"))
      (libsource (lib "LimeFPGAboard_schLib") (part "BSC093N04LS_G"))
    )
    (comp (ref "VT7")
      (value "BSC093N04LS G")
      (footprint "BSC093N04LS_G")
      (fields (field (name "MANUFACTURER") "Infineon Technologies") (field (name "ASSEMBLY INFO") "NF"))
      (libsource (lib "LimeFPGAboard_schLib") (part "BSC093N04LS_G"))
    )
  )
  (nets
    (net (code "1") (name "GND") (class "Default")
      (node (ref "C366") (pin "1") (pinfunction "1_1") (pintype "passive"))
      (node (ref "C367") (pin "2") (pinfunction "2_2") (pintype "passive"))
      (node (ref "C368") (pin "1") (pinfunction "1_1") (pintype "passive"))
      (node (ref "C369") (pin "1") (pinfunction "1_1") (pintype "passive"))
      (node (ref "C370") (pin "1") (pinfunction "1_1") (pintype "passive"))
      (node (ref "C371") (pin "1") (pinfunction "1_1") (pintype "passive"))
      (node (ref "C372") (pin "1") (pinfunction "1_1") (pintype "passive"))
      (node (ref "C373") (pin "2") (pinfunction "2_2") (pintype "passive"))
      (node (ref "C374") (pin "2") (pinfunction "2_2") (pintype "passive"))
      (node (ref "C375") (pin "1") (pinfunction "1_1") (pintype "passive"))
      (node (ref "C376") (pin "1") (pinfunction "1_1") (pintype "passive"))
      (node (ref "C377") (pin "2") (pinfunction "2_2") (pintype "passive"))
      (node (ref "C379") (pin "1") (pinfunction "1_1") (pintype "passive"))
      (node (ref "C380") (pin "1") (pinfunction "1_1") (pintype "passive"))
      (node (ref "C381") (pin "1") (pinfunction "1_1") (pintype "passive"))
      (node (ref "C382") (pin "1") (pinfunction "1_1") (pintype "passive"))
      (node (ref "C383") (pin "1") (pinfunction "1_1") (pintype "passive"))
      (node (ref "C384") (pin "1") (pinfunction "1_1") (pintype "passive"))
      (node (ref "C385") (pin "1") (pinfunction "1_1") (pintype "passive"))
      (node (ref "C386") (pin "1") (pinfunction "1_1") (pintype "passive"))
      (node (ref "C387") (pin "2") (pinfunction "2_2") (pintype "passive"))
      (node (ref "C388") (pin "1") (pinfunction "1_1") (pintype "passive"))
      (node (ref "C389") (pin "1") (pinfunction "1_1") (pintype "passive"))
      (node (ref "C390") (pin "1") (pinfunction "1_1") (pintype "passive"))
      (node (ref "C391") (pin "2") (pinfunction "2_2") (pintype "passive"))
      (node (ref "C392") (pin "2") (pinfunction "2_2") (pintype "passive"))
      (node (ref "C393") (pin "1") (pinfunction "1_1") (pintype "passive"))
      (node (ref "C394") (pin "2") (pinfunction "2_2") (pintype "passive"))
      (node (ref "C395") (pin "1") (pinfunction "1_1") (pintype "passive"))
      (node (ref "C396") (pin "1") (pinfunction "1_1") (pintype "passive"))
      (node (ref "C397") (pin "2") (pinfunction "2_2") (pintype "passive"))
      (node (ref "C399") (pin "1") (pinfunction "1_1") (pintype "passive"))
      (node (ref "C400") (pin "1") (pinfunction "1_1") (pintype "passive"))
      (node (ref "C401") (pin "1") (pinfunction "1_1") (pintype "passive"))
      (node (ref "C402") (pin "1") (pinfunction "1_1") (pintype "passive"))
      (node (ref "C403") (pin "1") (pinfunction "1_1") (pintype "passive"))
      (node (ref "C404") (pin "1") (pinfunction "1_1") (pintype "passive"))
      (node (ref "C405") (pin "1") (pinfunction "1_1") (pintype "passive"))
      (node (ref "C406") (pin "1") (pinfunction "1_1") (pintype "passive"))
      (node (ref "C407") (pin "1") (pinfunction "1_1") (pintype "passive"))
      (node (ref "C408") (pin "2") (pinfunction "2_2") (pintype "passive"))
      (node (ref "C409") (pin "2") (pinfunction "2_2") (pintype "passive"))
      (node (ref "C410") (pin "2") (pinfunction "2_2") (pintype "passive"))
      (node (ref "C411") (pin "2") (pinfunction "2_2") (pintype "passive"))
      (node (ref "C412") (pin "1") (pinfunction "1_1") (pintype "passive"))
      (node (ref "C413") (pin "1") (pinfunction "1_1") (pintype "passive"))
      (node (ref "C414") (pin "1") (pinfunction "1_1") (pintype "passive"))
      (node (ref "C415") (pin "1") (pinfunction "1_1") (pintype "passive"))
      (node (ref "C416") (pin "1") (pinfunction "1_1") (pintype "passive"))
      (node (ref "C417") (pin "1") (pinfunction "1_1") (pintype "passive"))
      (node (ref "C418") (pin "1") (pinfunction "1_1") (pintype "passive"))
      (node (ref "C419") (pin "1") (pinfunction "1_1") (pintype "passive"))
      (node (ref "C420") (pin "1") (pinfunction "1_1") (pintype "passive"))
      (node (ref "C421") (pin "1") (pinfunction "1_1") (pintype "passive"))
      (node (ref "IC20") (pin "4") (pinfunction "GND_4") (pintype "passive"))
      (node (ref "IC20") (pin "9") (pinfunction "PAD_9") (pintype "passive"))
      (node (ref "IC21") (pin "4") (pinfunction "GND_4") (pintype "passive"))
      (node (ref "IC21") (pin "7") (pinfunction "GND_7") (pintype "passive"))
      (node (ref "IC23") (pin "10") (pinfunction "PGND_10") (pintype "passive"))
      (node (ref "IC23") (pin "11") (pinfunction "PGND_11") (pintype "passive"))
      (node (ref "IC23") (pin "12") (pinfunction "PGND_12") (pintype "passive"))
      (node (ref "IC23") (pin "13") (pinfunction "PGND_13") (pintype "passive"))
      (node (ref "IC23") (pin "25") (pinfunction "GND_25") (pintype "passive"))
      (node (ref "IC23") (pin "4") (pinfunction "GND_4") (pintype "passive"))
      (node (ref "IC23") (pin "8") (pinfunction "PGND_8") (pintype "passive"))
      (node (ref "IC23") (pin "9") (pinfunction "PGND_9") (pintype "passive"))
      (node (ref "IC24") (pin "4") (pinfunction "GND_4") (pintype "passive"))
      (node (ref "IC24") (pin "9") (pinfunction "PAD_9") (pintype "passive"))
      (node (ref "IC25") (pin "11") (pinfunction "GND_11") (pintype "passive"))
      (node (ref "IC25") (pin "4") (pinfunction "PGND_4") (pintype "passive"))
      (node (ref "IC25") (pin "8") (pinfunction "GND_8") (pintype "passive"))
      (node (ref "IC26") (pin "4") (pinfunction "GND_4") (pintype "passive"))
      (node (ref "IC26") (pin "9") (pinfunction "PAD_9") (pintype "passive"))
      (node (ref "IC27") (pin "10") (pinfunction "PGND_10") (pintype "passive"))
      (node (ref "IC27") (pin "11") (pinfunction "PGND_11") (pintype "passive"))
      (node (ref "IC27") (pin "12") (pinfunction "PGND_12") (pintype "passive"))
      (node (ref "IC27") (pin "13") (pinfunction "PGND_13") (pintype "passive"))
      (node (ref "IC27") (pin "25") (pinfunction "GND_25") (pintype "passive"))
      (node (ref "IC27") (pin "4") (pinfunction "GND_4") (pintype "passive"))
      (node (ref "IC27") (pin "8") (pinfunction "PGND_8") (pintype "passive"))
      (node (ref "IC27") (pin "9") (pinfunction "PGND_9") (pintype "passive"))
      (node (ref "IC28") (pin "4") (pinfunction "GND_4") (pintype "passive"))
      (node (ref "IC28") (pin "9") (pinfunction "PAD_9") (pintype "passive"))
      (node (ref "IC29") (pin "4") (pinfunction "GND_4") (pintype "passive"))
      (node (ref "IC29") (pin "9") (pinfunction "PAD_9") (pintype "passive"))
      (node (ref "IC30") (pin "3") (pinfunction "GND_3") (pintype "passive"))
      (node (ref "IC31") (pin "4") (pinfunction "GND_4") (pintype "passive"))
      (node (ref "IC31") (pin "9") (pinfunction "PAD_9") (pintype "passive"))
      (node (ref "IC32") (pin "7") (pinfunction "GND_7") (pintype "passive"))
      (node (ref "IC32") (pin "9") (pinfunction "PAD_9") (pintype "passive"))
      (node (ref "J17") (pin "2") (pinfunction "2_2") (pintype "passive"))
      (node (ref "J17") (pin "3") (pinfunction "3_3") (pintype "passive"))
      (node (ref "J18") (pin "1") (pinfunction "1_1") (pintype "passive"))
      (node (ref "LED9") (pin "K") (pinfunction "C_K") (pintype "power_in"))
      (node (ref "MECH11") (pin "MH1") (pinfunction "MH1_MH1") (pintype "passive"))
      (node (ref "MECH12") (pin "MH1") (pinfunction "MH1_MH1") (pintype "passive"))
      (node (ref "MECH13") (pin "MH1") (pinfunction "MH1_MH1") (pintype "passive"))
      (node (ref "MECH14") (pin "MH1") (pinfunction "MH1_MH1") (pintype "passive"))
      (node (ref "R144") (pin "2") (pinfunction "2_2") (pintype "passive"))
      (node (ref "R148") (pin "2") (pinfunction "2_2") (pintype "passive"))
      (node (ref "R150") (pin "1") (pinfunction "1_1") (pintype "passive"))
      (node (ref "R151") (pin "2") (pinfunction "2_2") (pintype "passive"))
      (node (ref "R152") (pin "1") (pinfunction "1_1") (pintype "passive"))
      (node (ref "R158") (pin "1") (pinfunction "1_1") (pintype "passive"))
      (node (ref "R164") (pin "1") (pinfunction "1_1") (pintype "passive"))
      (node (ref "R165") (pin "2") (pinfunction "2_2") (pintype "passive"))
      (node (ref "R166") (pin "2") (pinfunction "2_2") (pintype "passive"))
      (node (ref "R167") (pin "1") (pinfunction "1_1") (pintype "passive"))
      (node (ref "R168") (pin "2") (pinfunction "2_2") (pintype "passive"))
      (node (ref "R174") (pin "2") (pinfunction "2_2") (pintype "passive"))
      (node (ref "R175") (pin "2") (pinfunction "2_2") (pintype "passive"))
      (node (ref "R177") (pin "1") (pinfunction "1_1") (pintype "passive"))
      (node (ref "TP1") (pin "1") (pintype "passive"))
      (node (ref "TP2") (pin "1") (pintype "passive"))
      (node (ref "VD1") (pin "2") (pinfunction "2_2") (pintype "passive"))
    )
    (net (code "2") (name "Net-(C378-Pad2)") (class "Default")
      (node (ref "C378") (pin "2") (pinfunction "2_2") (pintype "passive"))
      (node (ref "IC23") (pin "14") (pinfunction "SW_14") (pintype "passive"))
      (node (ref "IC23") (pin "26") (pinfunction "SW_26") (pintype "passive"))
      (node (ref "IC23") (pin "5") (pinfunction "SW_5") (pintype "passive"))
      (node (ref "IC23") (pin "6") (pinfunction "SW_6") (pintype "passive"))
      (node (ref "IC23") (pin "7") (pinfunction "SW_7") (pintype "passive"))
      (node (ref "L1") (pin "1") (pinfunction "1_1") (pintype "passive"))
    )
    (net (code "3") (name "Net-(C392-Pad1)") (class "Default")
      (node (ref "C392") (pin "1") (pinfunction "1_1") (pintype "passive"))
      (node (ref "R153") (pin "1") (pinfunction "1_1") (pintype "passive"))
    )
    (net (code "4") (name "Net-(C398-Pad2)") (class "Default")
      (node (ref "C398") (pin "2") (pinfunction "2_2") (pintype "passive"))
      (node (ref "IC27") (pin "14") (pinfunction "SW_14") (pintype "passive"))
      (node (ref "IC27") (pin "26") (pinfunction "SW_26") (pintype "passive"))
      (node (ref "IC27") (pin "5") (pinfunction "SW_5") (pintype "passive"))
      (node (ref "IC27") (pin "6") (pinfunction "SW_6") (pintype "passive"))
      (node (ref "IC27") (pin "7") (pinfunction "SW_7") (pintype "passive"))
      (node (ref "L2") (pin "1") (pinfunction "1_1") (pintype "passive"))
    )
    (net (code "5") (name "Net-(C410-Pad1)") (class "Default")
      (node (ref "C410") (pin "1") (pinfunction "1_1") (pintype "passive"))
      (node (ref "R169") (pin "1") (pinfunction "1_1") (pintype "passive"))
    )
    (net (code "6") (name "Net-(IC20-ADJ{slash}NC)") (class "Default")
      (node (ref "IC20") (pin "3") (pinfunction "ADJ/NC_3") (pintype "passive"))
      (node (ref "R143") (pin "1") (pinfunction "1_1") (pintype "passive"))
      (node (ref "R144") (pin "1") (pinfunction "1_1") (pintype "passive"))
    )
    (net (code "7") (name "Net-(IC20-OUT)") (class "Default")
      (node (ref "C376") (pin "2") (pinfunction "2_2") (pintype "passive"))
      (node (ref "IC20") (pin "1") (pinfunction "OUT_1") (pintype "output"))
      (node (ref "R142") (pin "2") (pinfunction "2_2") (pintype "passive"))
      (node (ref "R143") (pin "2") (pinfunction "2_2") (pintype "passive"))
    )
    (net (code "8") (name "Net-(IC21-GATE)") (class "Default")
      (node (ref "IC21") (pin "3") (pinfunction "GATE_3") (pintype "passive"))
      (node (ref "VT7") (pin "4") (pinfunction "G_4") (pintype "passive"))
    )
    (net (code "9") (name "Net-(IC22-GATE)") (class "Default")
      (node (ref "IC22") (pin "3") (pinfunction "GATE_3") (pintype "passive"))
      (node (ref "VT6") (pin "4") (pinfunction "G_4") (pintype "passive"))
    )
    (net (code "10") (name "Net-(IC22-GND-Pad4)") (class "Default")
      (node (ref "IC22") (pin "4") (pinfunction "GND_4") (pintype "passive"))
      (node (ref "IC22") (pin "7") (pinfunction "GND_7") (pintype "passive"))
      (node (ref "VD1") (pin "3") (pinfunction "3_3") (pintype "passive"))
    )
    (net (code "11") (name "Net-(IC22-IN)") (class "Default")
      (node (ref "C374") (pin "1") (pinfunction "1_1") (pintype "passive"))
      (node (ref "IC22") (pin "2") (pinfunction "IN_2") (pintype "passive"))
      (node (ref "J17") (pin "1") (pinfunction "1_1") (pintype "passive"))
      (node (ref "R139") (pin "2") (pinfunction "2_2") (pintype "passive"))
      (node (ref "VD1") (pin "1") (pinfunction "1_1") (pintype "passive"))
      (node (ref "VT6") (pin "1") (pinfunction "S_1") (pintype "passive"))
      (node (ref "VT6") (pin "2") (pinfunction "S_2") (pintype "passive"))
      (node (ref "VT6") (pin "3") (pinfunction "S_3") (pintype "passive"))
    )
    (net (code "12") (name "Net-(IC23-BST)") (class "Default")
      (node (ref "C378") (pin "1") (pinfunction "1_1") (pintype "passive"))
      (node (ref "IC23") (pin "15") (pinfunction "BST_15") (pintype "passive"))
    )
    (net (code "13") (name "Net-(IC23-COMP)") (class "Default")
      (node (ref "C391") (pin "1") (pinfunction "1_1") (pintype "passive"))
      (node (ref "IC23") (pin "1") (pinfunction "COMP_1") (pintype "passive"))
      (node (ref "R153") (pin "2") (pinfunction "2_2") (pintype "passive"))
    )
    (net (code "14") (name "Net-(IC23-FB)") (class "Default")
      (node (ref "IC23") (pin "2") (pinfunction "FB_2") (pintype "passive"))
      (node (ref "R149") (pin "2") (pinfunction "2_2") (pintype "passive"))
      (node (ref "R152") (pin "2") (pinfunction "2_2") (pintype "passive"))
    )
    (net (code "15") (name "Net-(IC23-RT)") (class "Default")
      (node (ref "IC23") (pin "22") (pinfunction "RT_22") (pintype "passive"))
      (node (ref "R151") (pin "1") (pinfunction "1_1") (pintype "passive"))
    )
    (net (code "16") (name "Net-(IC23-SS)") (class "Default")
      (node (ref "C394") (pin "1") (pinfunction "1_1") (pintype "passive"))
      (node (ref "IC23") (pin "24") (pinfunction "SS_24") (pintype "passive"))
    )
    (net (code "17") (name "Net-(IC23-SYNC)") (class "Default")
      (node (ref "IC23") (pin "23") (pinfunction "SYNC_23") (pintype "passive"))
      (node (ref "R150") (pin "2") (pinfunction "2_2") (pintype "passive"))
    )
    (net (code "18") (name "Net-(IC23-VREG)") (class "Default")
      (node (ref "C387") (pin "1") (pinfunction "1_1") (pintype "passive"))
      (node (ref "IC23") (pin "3") (pinfunction "VREG_3") (pintype "passive"))
    )
    (net (code "19") (name "Net-(IC24-ADJ{slash}NC)") (class "Default")
      (node (ref "IC24") (pin "3") (pinfunction "ADJ/NC_3") (pintype "passive"))
      (node (ref "R147") (pin "1") (pinfunction "1_1") (pintype "passive"))
      (node (ref "R148") (pin "1") (pinfunction "1_1") (pintype "passive"))
    )
    (net (code "20") (name "Net-(IC24-EN)") (class "Default")
      (node (ref "C381") (pin "2") (pinfunction "2_2") (pintype "passive"))
      (node (ref "FR51") (pin "2") (pinfunction "2_2") (pintype "passive"))
      (node (ref "IC24") (pin "5") (pinfunction "EN_5") (pintype "input"))
      (node (ref "IC24") (pin "8") (pinfunction "IN_8") (pintype "input"))
    )
    (net (code "21") (name "Net-(IC24-OUT)") (class "Default")
      (node (ref "C382") (pin "2") (pinfunction "2_2") (pintype "passive"))
      (node (ref "IC24") (pin "1") (pinfunction "OUT_1") (pintype "output"))
      (node (ref "R146") (pin "2") (pinfunction "2_2") (pintype "passive"))
      (node (ref "R147") (pin "2") (pinfunction "2_2") (pintype "passive"))
    )
    (net (code "22") (name "Net-(IC25-S3)") (class "Default")
      (node (ref "IC25") (pin "7") (pinfunction "S3_7") (pintype "passive"))
      (node (ref "R156") (pin "2") (pinfunction "2_2") (pintype "passive"))
    )
    (net (code "23") (name "Net-(IC25-S5)") (class "Default")
      (node (ref "IC25") (pin "9") (pinfunction "S5_9") (pintype "passive"))
      (node (ref "R154") (pin "2") (pinfunction "2_2") (pintype "passive"))
    )
    (net (code "24") (name "Net-(IC26-ADJ{slash}NC)") (class "Default")
      (node (ref "IC26") (pin "3") (pinfunction "ADJ/NC_3") (pintype "passive"))
      (node (ref "R157") (pin "2") (pinfunction "2_2") (pintype "passive"))
      (node (ref "R158") (pin "2") (pinfunction "2_2") (pintype "passive"))
    )
    (net (code "25") (name "Net-(IC26-EN)") (class "Default")
      (node (ref "C389") (pin "2") (pinfunction "2_2") (pintype "passive"))
      (node (ref "FR52") (pin "2") (pinfunction "2_2") (pintype "passive"))
      (node (ref "IC26") (pin "5") (pinfunction "EN_5") (pintype "input"))
      (node (ref "IC26") (pin "8") (pinfunction "IN_8") (pintype "input"))
    )
    (net (code "26") (name "Net-(IC26-OUT)") (class "Default")
      (node (ref "C390") (pin "2") (pinfunction "2_2") (pintype "passive"))
      (node (ref "IC26") (pin "1") (pinfunction "OUT_1") (pintype "output"))
      (node (ref "R155") (pin "2") (pinfunction "2_2") (pintype "passive"))
      (node (ref "R157") (pin "1") (pinfunction "1_1") (pintype "passive"))
    )
    (net (code "27") (name "Net-(IC27-BST)") (class "Default")
      (node (ref "C398") (pin "1") (pinfunction "1_1") (pintype "passive"))
      (node (ref "IC27") (pin "15") (pinfunction "BST_15") (pintype "passive"))
    )
    (net (code "28") (name "Net-(IC27-COMP)") (class "Default")
      (node (ref "C409") (pin "1") (pinfunction "1_1") (pintype "passive"))
      (node (ref "IC27") (pin "1") (pinfunction "COMP_1") (pintype "passive"))
      (node (ref "R169") (pin "2") (pinfunction "2_2") (pintype "passive"))
    )
    (net (code "29") (name "Net-(IC27-FB)") (class "Default")
      (node (ref "IC27") (pin "2") (pinfunction "FB_2") (pintype "passive"))
      (node (ref "R163") (pin "2") (pinfunction "2_2") (pintype "passive"))
      (node (ref "R168") (pin "1") (pinfunction "1_1") (pintype "passive"))
    )
    (net (code "30") (name "Net-(IC27-RT)") (class "Default")
      (node (ref "IC27") (pin "22") (pinfunction "RT_22") (pintype "passive"))
      (node (ref "R165") (pin "1") (pinfunction "1_1") (pintype "passive"))
    )
    (net (code "31") (name "Net-(IC27-SS)") (class "Default")
      (node (ref "C411") (pin "1") (pinfunction "1_1") (pintype "passive"))
      (node (ref "IC27") (pin "24") (pinfunction "SS_24") (pintype "passive"))
    )
    (net (code "32") (name "Net-(IC27-SYNC)") (class "Default")
      (node (ref "IC27") (pin "23") (pinfunction "SYNC_23") (pintype "passive"))
      (node (ref "R164") (pin "2") (pinfunction "2_2") (pintype "passive"))
    )
    (net (code "33") (name "Net-(IC27-VREG)") (class "Default")
      (node (ref "C408") (pin "1") (pinfunction "1_1") (pintype "passive"))
      (node (ref "IC27") (pin "3") (pinfunction "VREG_3") (pintype "passive"))
    )
    (net (code "34") (name "Net-(IC28-ADJ{slash}NC)") (class "Default")
      (node (ref "IC28") (pin "3") (pinfunction "ADJ/NC_3") (pintype "passive"))
      (node (ref "R161") (pin "1") (pinfunction "1_1") (pintype "passive"))
      (node (ref "R166") (pin "1") (pinfunction "1_1") (pintype "passive"))
    )
    (net (code "35") (name "Net-(IC28-OUT)") (class "Default")
      (node (ref "C401") (pin "2") (pinfunction "2_2") (pintype "passive"))
      (node (ref "IC28") (pin "1") (pinfunction "OUT_1") (pintype "output"))
      (node (ref "R159") (pin "2") (pinfunction "2_2") (pintype "passive"))
      (node (ref "R161") (pin "2") (pinfunction "2_2") (pintype "passive"))
    )
    (net (code "36") (name "Net-(IC29-ADJ{slash}NC)") (class "Default")
      (node (ref "IC29") (pin "3") (pinfunction "ADJ/NC_3") (pintype "passive"))
      (node (ref "R162") (pin "1") (pinfunction "1_1") (pintype "passive"))
      (node (ref "R167") (pin "2") (pinfunction "2_2") (pintype "passive"))
    )
    (net (code "37") (name "Net-(IC29-EN)") (class "Default")
      (node (ref "C403") (pin "2") (pinfunction "2_2") (pintype "passive"))
      (node (ref "FR53") (pin "2") (pinfunction "2_2") (pintype "passive"))
      (node (ref "IC29") (pin "5") (pinfunction "EN_5") (pintype "input"))
      (node (ref "IC29") (pin "8") (pinfunction "IN_8") (pintype "input"))
    )
    (net (code "38") (name "Net-(IC29-OUT)") (class "Default")
      (node (ref "C404") (pin "2") (pinfunction "2_2") (pintype "passive"))
      (node (ref "IC29") (pin "1") (pinfunction "OUT_1") (pintype "output"))
      (node (ref "R160") (pin "2") (pinfunction "2_2") (pintype "passive"))
      (node (ref "R162") (pin "2") (pinfunction "2_2") (pintype "passive"))
    )
    (net (code "39") (name "Net-(IC30-ADJUST)") (class "Default")
      (node (ref "IC30") (pin "5") (pinfunction "ADJUST_5") (pintype "passive"))
      (node (ref "R172") (pin "2") (pinfunction "2_2") (pintype "passive"))
      (node (ref "R174") (pin "1") (pinfunction "1_1") (pintype "passive"))
    )
    (net (code "40") (name "Net-(IC30-IN)") (class "Default")
      (node (ref "C414") (pin "2") (pinfunction "2_2") (pintype "passive"))
      (node (ref "FR54") (pin "2") (pinfunction "2_2") (pintype "passive"))
      (node (ref "IC30") (pin "2") (pinfunction "IN_2") (pintype "passive"))
    )
    (net (code "41") (name "Net-(IC30-OUT)") (class "Default")
      (node (ref "C413") (pin "2") (pinfunction "2_2") (pintype "passive"))
      (node (ref "IC30") (pin "4") (pinfunction "OUT_4") (pintype "passive"))
      (node (ref "R170") (pin "2") (pinfunction "2_2") (pintype "passive"))
      (node (ref "R172") (pin "1") (pinfunction "1_1") (pintype "passive"))
    )
    (net (code "42") (name "Net-(IC31-ADJ{slash}NC)") (class "Default")
      (node (ref "IC31") (pin "3") (pinfunction "ADJ/NC_3") (pintype "passive"))
      (node (ref "R173") (pin "1") (pinfunction "1_1") (pintype "passive"))
      (node (ref "R175") (pin "1") (pinfunction "1_1") (pintype "passive"))
    )
    (net (code "43") (name "Net-(IC31-OUT)") (class "Default")
      (node (ref "C416") (pin "2") (pinfunction "2_2") (pintype "passive"))
      (node (ref "IC31") (pin "1") (pinfunction "OUT_1") (pintype "output"))
      (node (ref "R171") (pin "2") (pinfunction "2_2") (pintype "passive"))
      (node (ref "R173") (pin "2") (pinfunction "2_2") (pintype "passive"))
    )
    (net (code "44") (name "Net-(IC32-ADJ{slash}BYP)") (class "Default")
      (node (ref "IC32") (pin "8") (pinfunction "ADJ/BYP_8") (pintype "input"))
      (node (ref "R176") (pin "2") (pinfunction "2_2") (pintype "passive"))
      (node (ref "R177") (pin "2") (pinfunction "2_2") (pintype "passive"))
    )
    (net (code "45") (name "Net-(IC32-EN)") (class "Default")
      (node (ref "C421") (pin "2") (pinfunction "2_2") (pintype "passive"))
      (node (ref "IC32") (pin "1") (pinfunction "EN_1") (pintype "input"))
      (node (ref "R178") (pin "2") (pinfunction "2_2") (pintype "passive"))
      (node (ref "R179") (pin "1") (pinfunction "1_1") (pintype "passive"))
    )
    (net (code "46") (name "Net-(IC32-VIN)") (class "Default")
      (node (ref "C420") (pin "2") (pinfunction "2_2") (pintype "passive"))
      (node (ref "FR55") (pin "2") (pinfunction "2_2") (pintype "passive"))
      (node (ref "IC32") (pin "3") (pinfunction "VIN_3") (pintype "input"))
    )
    (net (code "47") (name "Net-(IC32-VOUT)") (class "Default")
      (node (ref "C417") (pin "2") (pinfunction "2_2") (pintype "passive"))
      (node (ref "FR56") (pin "1") (pinfunction "1_1") (pintype "passive"))
      (node (ref "IC32") (pin "5") (pinfunction "VOUT_5") (pintype "output"))
      (node (ref "R176") (pin "1") (pinfunction "1_1") (pintype "passive"))
    )
    (net (code "48") (name "Net-(LED9-PadA)") (class "Default")
      (node (ref "LED9") (pin "A") (pinfunction "A_A") (pintype "power_in"))
      (node (ref "R145") (pin "1") (pinfunction "1_1") (pintype "passive"))
    )
    (net (code "49") (name "VCC1P2") (class "Default")
      (node (ref "C405") (pin "2") (pinfunction "2_2") (pintype "passive"))
      (node (ref "C406") (pin "2") (pinfunction "2_2") (pintype "passive"))
      (node (ref "C407") (pin "2") (pinfunction "2_2") (pintype "passive"))
      (node (ref "L2") (pin "2") (pinfunction "2_2") (pintype "passive"))
      (node (ref "R163") (pin "1") (pinfunction "1_1") (pintype "passive"))
    )
    (net (code "50") (name "VCC1P4_LMS") (class "Default")
      (node (ref "R155") (pin "1") (pinfunction "1_1") (pintype "passive"))
    )
    (net (code "51") (name "VCC1P8") (class "Default")
      (node (ref "R171") (pin "1") (pinfunction "1_1") (pintype "passive"))
    )
    (net (code "52") (name "VCC1P8_DDR2") (class "Default")
      (node (ref "C386") (pin "2") (pinfunction "2_2") (pintype "passive"))
      (node (ref "IC25") (pin "1") (pinfunction "VDDQSNS_1") (pintype "passive"))
      (node (ref "IC25") (pin "2") (pinfunction "VLDOIN_2") (pintype "passive"))
      (node (ref "R159") (pin "1") (pinfunction "1_1") (pintype "passive"))
    )
    (net (code "53") (name "VCC1P8_LMS") (class "Default")
      (node (ref "R146") (pin "1") (pinfunction "1_1") (pintype "passive"))
    )
    (net (code "54") (name "VCC1P25_LMS") (class "Default")
      (node (ref "R160") (pin "1") (pinfunction "1_1") (pintype "passive"))
    )
    (net (code "55") (name "VCC1P25_LMS_DIG") (class "Default")
      (node (ref "R170") (pin "1") (pinfunction "1_1") (pintype "passive"))
    )
    (net (code "56") (name "VCC2P5") (class "Default")
      (node (ref "R141") (pin "2") (pinfunction "2_2") (pintype "passive"))
      (node (ref "R142") (pin "1") (pinfunction "1_1") (pintype "passive"))
      (node (ref "R178") (pin "1") (pinfunction "1_1") (pintype "passive"))
    )
    (net (code "57") (name "VCC3P3") (class "Default")
      (node (ref "C375") (pin "2") (pinfunction "2_2") (pintype "passive"))
      (node (ref "C380") (pin "2") (pinfunction "2_2") (pintype "passive"))
      (node (ref "C383") (pin "2") (pinfunction "2_2") (pintype "passive"))
      (node (ref "C384") (pin "2") (pinfunction "2_2") (pintype "passive"))
      (node (ref "C385") (pin "2") (pinfunction "2_2") (pintype "passive"))
      (node (ref "C388") (pin "2") (pinfunction "2_2") (pintype "passive"))
      (node (ref "C393") (pin "2") (pinfunction "2_2") (pintype "passive"))
      (node (ref "C400") (pin "2") (pinfunction "2_2") (pintype "passive"))
      (node (ref "C402") (pin "2") (pinfunction "2_2") (pintype "passive"))
      (node (ref "C412") (pin "2") (pinfunction "2_2") (pintype "passive"))
      (node (ref "C415") (pin "2") (pinfunction "2_2") (pintype "passive"))
      (node (ref "FR51") (pin "1") (pinfunction "1_1") (pintype "passive"))
      (node (ref "FR52") (pin "1") (pinfunction "1_1") (pintype "passive"))
      (node (ref "FR53") (pin "1") (pinfunction "1_1") (pintype "passive"))
      (node (ref "FR54") (pin "1") (pinfunction "1_1") (pintype "passive"))
      (node (ref "IC20") (pin "5") (pinfunction "EN_5") (pintype "input"))
      (node (ref "IC20") (pin "8") (pinfunction "IN_8") (pintype "input"))
      (node (ref "IC25") (pin "10") (pinfunction "VIN_10") (pintype "passive"))
      (node (ref "IC28") (pin "5") (pinfunction "EN_5") (pintype "input"))
      (node (ref "IC28") (pin "8") (pinfunction "IN_8") (pintype "input"))
      (node (ref "IC31") (pin "5") (pinfunction "EN_5") (pintype "input"))
      (node (ref "IC31") (pin "8") (pinfunction "IN_8") (pintype "input"))
      (node (ref "L1") (pin "2") (pinfunction "2_2") (pintype "passive"))
      (node (ref "R138") (pin "2") (pinfunction "2_2") (pintype "passive"))
      (node (ref "R145") (pin "2") (pinfunction "2_2") (pintype "passive"))
      (node (ref "R149") (pin "1") (pinfunction "1_1") (pintype "passive"))
      (node (ref "R154") (pin "1") (pinfunction "1_1") (pintype "passive"))
      (node (ref "R156") (pin "1") (pinfunction "1_1") (pintype "passive"))
    )
    (net (code "58") (name "VCC3P3_CLK") (class "Default")
      (node (ref "C418") (pin "2") (pinfunction "2_2") (pintype "passive"))
      (node (ref "FR56") (pin "2") (pinfunction "2_2") (pintype "passive"))
    )
    (net (code "59") (name "VCC12P0") (class "Default")
      (node (ref "C368") (pin "2") (pinfunction "2_2") (pintype "passive"))
      (node (ref "C369") (pin "2") (pinfunction "2_2") (pintype "passive"))
      (node (ref "C370") (pin "2") (pinfunction "2_2") (pintype "passive"))
      (node (ref "C371") (pin "2") (pinfunction "2_2") (pintype "passive"))
      (node (ref "C372") (pin "2") (pinfunction "2_2") (pintype "passive"))
      (node (ref "C373") (pin "1") (pinfunction "1_1") (pintype "passive"))
      (node (ref "C377") (pin "1") (pinfunction "1_1") (pintype "passive"))
      (node (ref "C379") (pin "2") (pinfunction "2_2") (pintype "passive"))
      (node (ref "C399") (pin "2") (pinfunction "2_2") (pintype "passive"))
      (node (ref "C419") (pin "2") (pinfunction "2_2") (pintype "passive"))
      (node (ref "FR55") (pin "1") (pinfunction "1_1") (pintype "passive"))
      (node (ref "IC21") (pin "1") (pinfunction "OUT_1") (pintype "passive"))
      (node (ref "IC21") (pin "6") (pinfunction "VDD_6") (pintype "passive"))
      (node (ref "IC22") (pin "1") (pinfunction "OUT_1") (pintype "passive"))
      (node (ref "IC22") (pin "6") (pinfunction "VDD_6") (pintype "passive"))
      (node (ref "IC23") (pin "16") (pinfunction "PVIN_16") (pintype "passive"))
      (node (ref "IC23") (pin "17") (pinfunction "PVIN_17") (pintype "passive"))
      (node (ref "IC23") (pin "18") (pinfunction "PVIN_18") (pintype "passive"))
      (node (ref "IC23") (pin "19") (pinfunction "PVIN_19") (pintype "passive"))
      (node (ref "IC23") (pin "20") (pinfunction "EN_20") (pintype "passive"))
      (node (ref "IC27") (pin "16") (pinfunction "PVIN_16") (pintype "passive"))
      (node (ref "IC27") (pin "17") (pinfunction "PVIN_17") (pintype "passive"))
      (node (ref "IC27") (pin "18") (pinfunction "PVIN_18") (pintype "passive"))
      (node (ref "IC27") (pin "19") (pinfunction "PVIN_19") (pintype "passive"))
      (node (ref "IC27") (pin "20") (pinfunction "EN_20") (pintype "passive"))
      (node (ref "J18") (pin "2") (pinfunction "2_2") (pintype "passive"))
      (node (ref "R139") (pin "1") (pinfunction "1_1") (pintype "passive"))
      (node (ref "R140") (pin "1") (pinfunction "1_1") (pintype "passive"))
      (node (ref "VT6") (pin "5") (pinfunction "D_5") (pintype "passive"))
      (node (ref "VT6") (pin "6") (pinfunction "D_6") (pintype "passive"))
      (node (ref "VT6") (pin "7") (pinfunction "D_7") (pintype "passive"))
      (node (ref "VT6") (pin "8") (pinfunction "D_8") (pintype "passive"))
      (node (ref "VT7") (pin "5") (pinfunction "D_5") (pintype "passive"))
      (node (ref "VT7") (pin "6") (pinfunction "D_6") (pintype "passive"))
      (node (ref "VT7") (pin "7") (pinfunction "D_7") (pintype "passive"))
      (node (ref "VT7") (pin "8") (pinfunction "D_8") (pintype "passive"))
    )
    (net (code "60") (name "VCC12P0_PCIE") (class "Default")
      (node (ref "IC21") (pin "2") (pinfunction "IN_2") (pintype "passive"))
      (node (ref "R140") (pin "2") (pinfunction "2_2") (pintype "passive"))
      (node (ref "VT7") (pin "1") (pinfunction "S_1") (pintype "passive"))
      (node (ref "VT7") (pin "2") (pinfunction "S_2") (pintype "passive"))
      (node (ref "VT7") (pin "3") (pinfunction "S_3") (pintype "passive"))
    )
    (net (code "61") (name "VDIO_LMS") (class "Default")
      (node (ref "C366") (pin "2") (pinfunction "2_2") (pintype "passive"))
      (node (ref "C367") (pin "1") (pinfunction "1_1") (pintype "passive"))
      (node (ref "FR50") (pin "2") (pinfunction "2_2") (pintype "passive"))
    )
    (net (code "62") (name "VDIO_LMS_FPGA") (class "Default")
      (node (ref "FR50") (pin "1") (pinfunction "1_1") (pintype "passive"))
      (node (ref "R138") (pin "1") (pinfunction "1_1") (pintype "passive"))
      (node (ref "R141") (pin "1") (pinfunction "1_1") (pintype "passive"))
      (node (ref "R179") (pin "2") (pinfunction "2_2") (pintype "passive"))
    )
    (net (code "63") (name "VREF_DDR2") (class "Default")
      (node (ref "C397") (pin "1") (pinfunction "1_1") (pintype "passive"))
      (node (ref "IC25") (pin "6") (pinfunction "VTTREF_6") (pintype "passive"))
    )
    (net (code "64") (name "VTT_DDR2") (class "Default")
      (node (ref "C395") (pin "2") (pinfunction "2_2") (pintype "passive"))
      (node (ref "C396") (pin "2") (pinfunction "2_2") (pintype "passive"))
      (node (ref "IC25") (pin "3") (pinfunction "VTT_3") (pintype "passive"))
      (node (ref "IC25") (pin "5") (pinfunction "VTTSNS_5") (pintype "passive"))
    )
    (net (code "65") (name "unconnected-(F1-Pad1)") (class "Default")
      (node (ref "F1") (pin "1") (pintype "passive+no_connect"))
    )
    (net (code "66") (name "unconnected-(F2-Pad1)") (class "Default")
      (node (ref "F2") (pin "1") (pintype "passive+no_connect"))
    )
    (net (code "67") (name "unconnected-(F3-Pad1)") (class "Default")
      (node (ref "F3") (pin "1") (pintype "passive+no_connect"))
    )
    (net (code "68") (name "unconnected-(F4-Pad1)") (class "Default")
      (node (ref "F4") (pin "1") (pintype "passive+no_connect"))
    )
    (net (code "69") (name "unconnected-(F5-Pad1)") (class "Default")
      (node (ref "F5") (pin "1") (pintype "passive+no_connect"))
    )
    (net (code "70") (name "unconnected-(F6-Pad1)") (class "Default")
      (node (ref "F6") (pin "1") (pintype "passive+no_connect"))
    )
    (net (code "71") (name "unconnected-(F7-Pad1)") (class "Default")
      (node (ref "F7") (pin "1") (pintype "passive+no_connect"))
    )
    (net (code "72") (name "unconnected-(F8-Pad1)") (class "Default")
      (node (ref "F8") (pin "1") (pintype "passive+no_connect"))
    )
    (net (code "73") (name "unconnected-(IC20-NC-Pad2)") (class "Default")
      (node (ref "IC20") (pin "2") (pinfunction "NC_2") (pintype "passive+no_connect"))
    )
    (net (code "74") (name "unconnected-(IC20-NC-Pad6)") (class "Default")
      (node (ref "IC20") (pin "6") (pinfunction "NC_6") (pintype "passive+no_connect"))
    )
    (net (code "75") (name "unconnected-(IC20-NC-Pad7)") (class "Default")
      (node (ref "IC20") (pin "7") (pinfunction "NC_7") (pintype "passive+no_connect"))
    )
    (net (code "76") (name "unconnected-(IC21-NC-Pad5)") (class "Default")
      (node (ref "IC21") (pin "5") (pinfunction "NC_5") (pintype "passive+no_connect"))
    )
    (net (code "77") (name "unconnected-(IC22-NC-Pad5)") (class "Default")
      (node (ref "IC22") (pin "5") (pinfunction "NC_5") (pintype "passive+no_connect"))
    )
    (net (code "78") (name "unconnected-(IC23-PGOOD-Pad21)") (class "Default")
      (node (ref "IC23") (pin "21") (pinfunction "PGOOD_21") (pintype "passive+no_connect"))
    )
    (net (code "79") (name "unconnected-(IC24-NC-Pad2)") (class "Default")
      (node (ref "IC24") (pin "2") (pinfunction "NC_2") (pintype "passive+no_connect"))
    )
    (net (code "80") (name "unconnected-(IC24-NC-Pad6)") (class "Default")
      (node (ref "IC24") (pin "6") (pinfunction "NC_6") (pintype "passive+no_connect"))
    )
    (net (code "81") (name "unconnected-(IC24-NC-Pad7)") (class "Default")
      (node (ref "IC24") (pin "7") (pinfunction "NC_7") (pintype "passive+no_connect"))
    )
    (net (code "82") (name "unconnected-(IC26-NC-Pad2)") (class "Default")
      (node (ref "IC26") (pin "2") (pinfunction "NC_2") (pintype "passive+no_connect"))
    )
    (net (code "83") (name "unconnected-(IC26-NC-Pad6)") (class "Default")
      (node (ref "IC26") (pin "6") (pinfunction "NC_6") (pintype "passive+no_connect"))
    )
    (net (code "84") (name "unconnected-(IC26-NC-Pad7)") (class "Default")
      (node (ref "IC26") (pin "7") (pinfunction "NC_7") (pintype "passive+no_connect"))
    )
    (net (code "85") (name "unconnected-(IC27-PGOOD-Pad21)") (class "Default")
      (node (ref "IC27") (pin "21") (pinfunction "PGOOD_21") (pintype "passive+no_connect"))
    )
    (net (code "86") (name "unconnected-(IC28-NC-Pad2)") (class "Default")
      (node (ref "IC28") (pin "2") (pinfunction "NC_2") (pintype "passive+no_connect"))
    )
    (net (code "87") (name "unconnected-(IC28-NC-Pad6)") (class "Default")
      (node (ref "IC28") (pin "6") (pinfunction "NC_6") (pintype "passive+no_connect"))
    )
    (net (code "88") (name "unconnected-(IC28-NC-Pad7)") (class "Default")
      (node (ref "IC28") (pin "7") (pinfunction "NC_7") (pintype "passive+no_connect"))
    )
    (net (code "89") (name "unconnected-(IC29-NC-Pad2)") (class "Default")
      (node (ref "IC29") (pin "2") (pinfunction "NC_2") (pintype "passive+no_connect"))
    )
    (net (code "90") (name "unconnected-(IC29-NC-Pad6)") (class "Default")
      (node (ref "IC29") (pin "6") (pinfunction "NC_6") (pintype "passive+no_connect"))
    )
    (net (code "91") (name "unconnected-(IC29-NC-Pad7)") (class "Default")
      (node (ref "IC29") (pin "7") (pinfunction "NC_7") (pintype "passive+no_connect"))
    )
    (net (code "92") (name "unconnected-(IC30-NC-Pad1)") (class "Default")
      (node (ref "IC30") (pin "1") (pinfunction "NC_1") (pintype "passive+no_connect"))
    )
    (net (code "93") (name "unconnected-(IC31-NC-Pad2)") (class "Default")
      (node (ref "IC31") (pin "2") (pinfunction "NC_2") (pintype "passive+no_connect"))
    )
    (net (code "94") (name "unconnected-(IC31-NC-Pad6)") (class "Default")
      (node (ref "IC31") (pin "6") (pinfunction "NC_6") (pintype "passive+no_connect"))
    )
    (net (code "95") (name "unconnected-(IC31-NC-Pad7)") (class "Default")
      (node (ref "IC31") (pin "7") (pinfunction "NC_7") (pintype "passive+no_connect"))
    )
    (net (code "96") (name "unconnected-(IC32-NC-Pad2)") (class "Default")
      (node (ref "IC32") (pin "2") (pinfunction "NC_2") (pintype "passive+no_connect"))
    )
    (net (code "97") (name "unconnected-(IC32-NC-Pad4)") (class "Default")
      (node (ref "IC32") (pin "4") (pinfunction "NC_4") (pintype "passive+no_connect"))
    )
    (net (code "98") (name "unconnected-(IC32-NC-Pad6)") (class "Default")
      (node (ref "IC32") (pin "6") (pinfunction "NC_6") (pintype "passive+no_connect"))
    )
  )
)
